# untitled.net
KiCad netlist of a schematic drawn in EAGLE
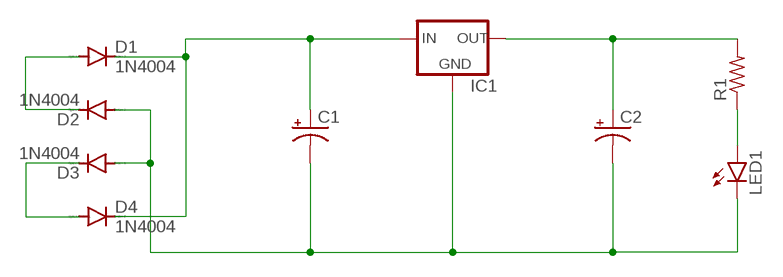
[diagram p0: schematic, sheet 1]

(export (version "E")
  (design (tool "Eeschema 10.0.6"))
  (components
    (comp (ref "C1")
      (value "CPOL-USTT2D7")
      (footprint "eagle-import:TT2D7")
      (libsource (lib "eagle-import") (part "CPOL-USTT2D7"))
    )
    (comp (ref "C2")
      (value "CPOL-USTT2D7")
      (footprint "eagle-import:TT2D7")
      (libsource (lib "eagle-import") (part "CPOL-USTT2D7"))
    )
    (comp (ref "D1")
      (value "1N4004")
      (footprint "eagle-import:DO41-10")
      (libsource (lib "eagle-import") (part "1N4004"))
    )
    (comp (ref "D2")
      (value "1N4004")
      (footprint "eagle-import:DO41-10")
      (libsource (lib "eagle-import") (part "1N4004"))
    )
    (comp (ref "D3")
      (value "1N4004")
      (footprint "eagle-import:DO41-10")
      (libsource (lib "eagle-import") (part "1N4004"))
    )
    (comp (ref "D4")
      (value "1N4004")
      (footprint "eagle-import:DO41-10")
      (libsource (lib "eagle-import") (part "1N4004"))
    )
    (comp (ref "IC1")
      (value "78XXL")
      (footprint "eagle-import:78XXL")
      (libsource (lib "eagle-import") (part "78XXL"))
    )
    (comp (ref "LED1")
      (value "LED5MM")
      (footprint "eagle-import:LED5MM")
      (libsource (lib "eagle-import") (part "LED5MM"))
    )
    (comp (ref "R1")
      (value "R-US_0207/10")
      (footprint "eagle-import:0207_10")
      (libsource (lib "eagle-import") (part "R-US_0207/10"))
    )
  )
  (nets
    (net (code "1") (name "Net-(C1-Pad+)") (class "Default")
      (node (ref "C1") (pin "+") (pinfunction "+_+") (pintype "passive"))
      (node (ref "D1") (pin "C") (pinfunction "C_C") (pintype "passive"))
      (node (ref "D4") (pin "C") (pinfunction "C_C") (pintype "passive"))
      (node (ref "IC1") (pin "IN") (pinfunction "IN_IN") (pintype "input"))
    )
    (net (code "2") (name "Net-(C2-Pad+)") (class "Default")
      (node (ref "C2") (pin "+") (pinfunction "+_+") (pintype "passive"))
      (node (ref "IC1") (pin "OUT") (pinfunction "OUT_OUT") (pintype "passive"))
      (node (ref "R1") (pin "2") (pinfunction "2_2") (pintype "passive"))
    )
    (net (code "3") (name "Net-(D1-PadA)") (class "Default")
      (node (ref "D1") (pin "A") (pinfunction "A_A") (pintype "passive"))
      (node (ref "D2") (pin "C") (pinfunction "C_C") (pintype "passive"))
    )
    (net (code "4") (name "Net-(D3-PadC)") (class "Default")
      (node (ref "D3") (pin "C") (pinfunction "C_C") (pintype "passive"))
      (node (ref "D4") (pin "A") (pinfunction "A_A") (pintype "passive"))
    )
    (net (code "5") (name "Net-(LED1-C)") (class "Default")
      (node (ref "C1") (pin "-") (pinfunction "-_-") (pintype "passive"))
      (node (ref "C2") (pin "-") (pinfunction "-_-") (pintype "passive"))
      (node (ref "D2") (pin "A") (pinfunction "A_A") (pintype "passive"))
      (node (ref "D3") (pin "A") (pinfunction "A_A") (pintype "passive"))
      (node (ref "IC1") (pin "GND") (pinfunction "GND_GND") (pintype "input"))
      (node (ref "LED1") (pin "K") (pinfunction "C_K") (pintype "passive"))
    )
    (net (code "6") (name "Net-(LED1-PadA)") (class "Default")
      (node (ref "LED1") (pin "A") (pinfunction "A_A") (pintype "passive"))
      (node (ref "R1") (pin "1") (pinfunction "1_1") (pintype "passive"))
    )
  )
)
